# ip_phone_f_power.net
KiCad netlist of a schematic drawn in Altium Designer
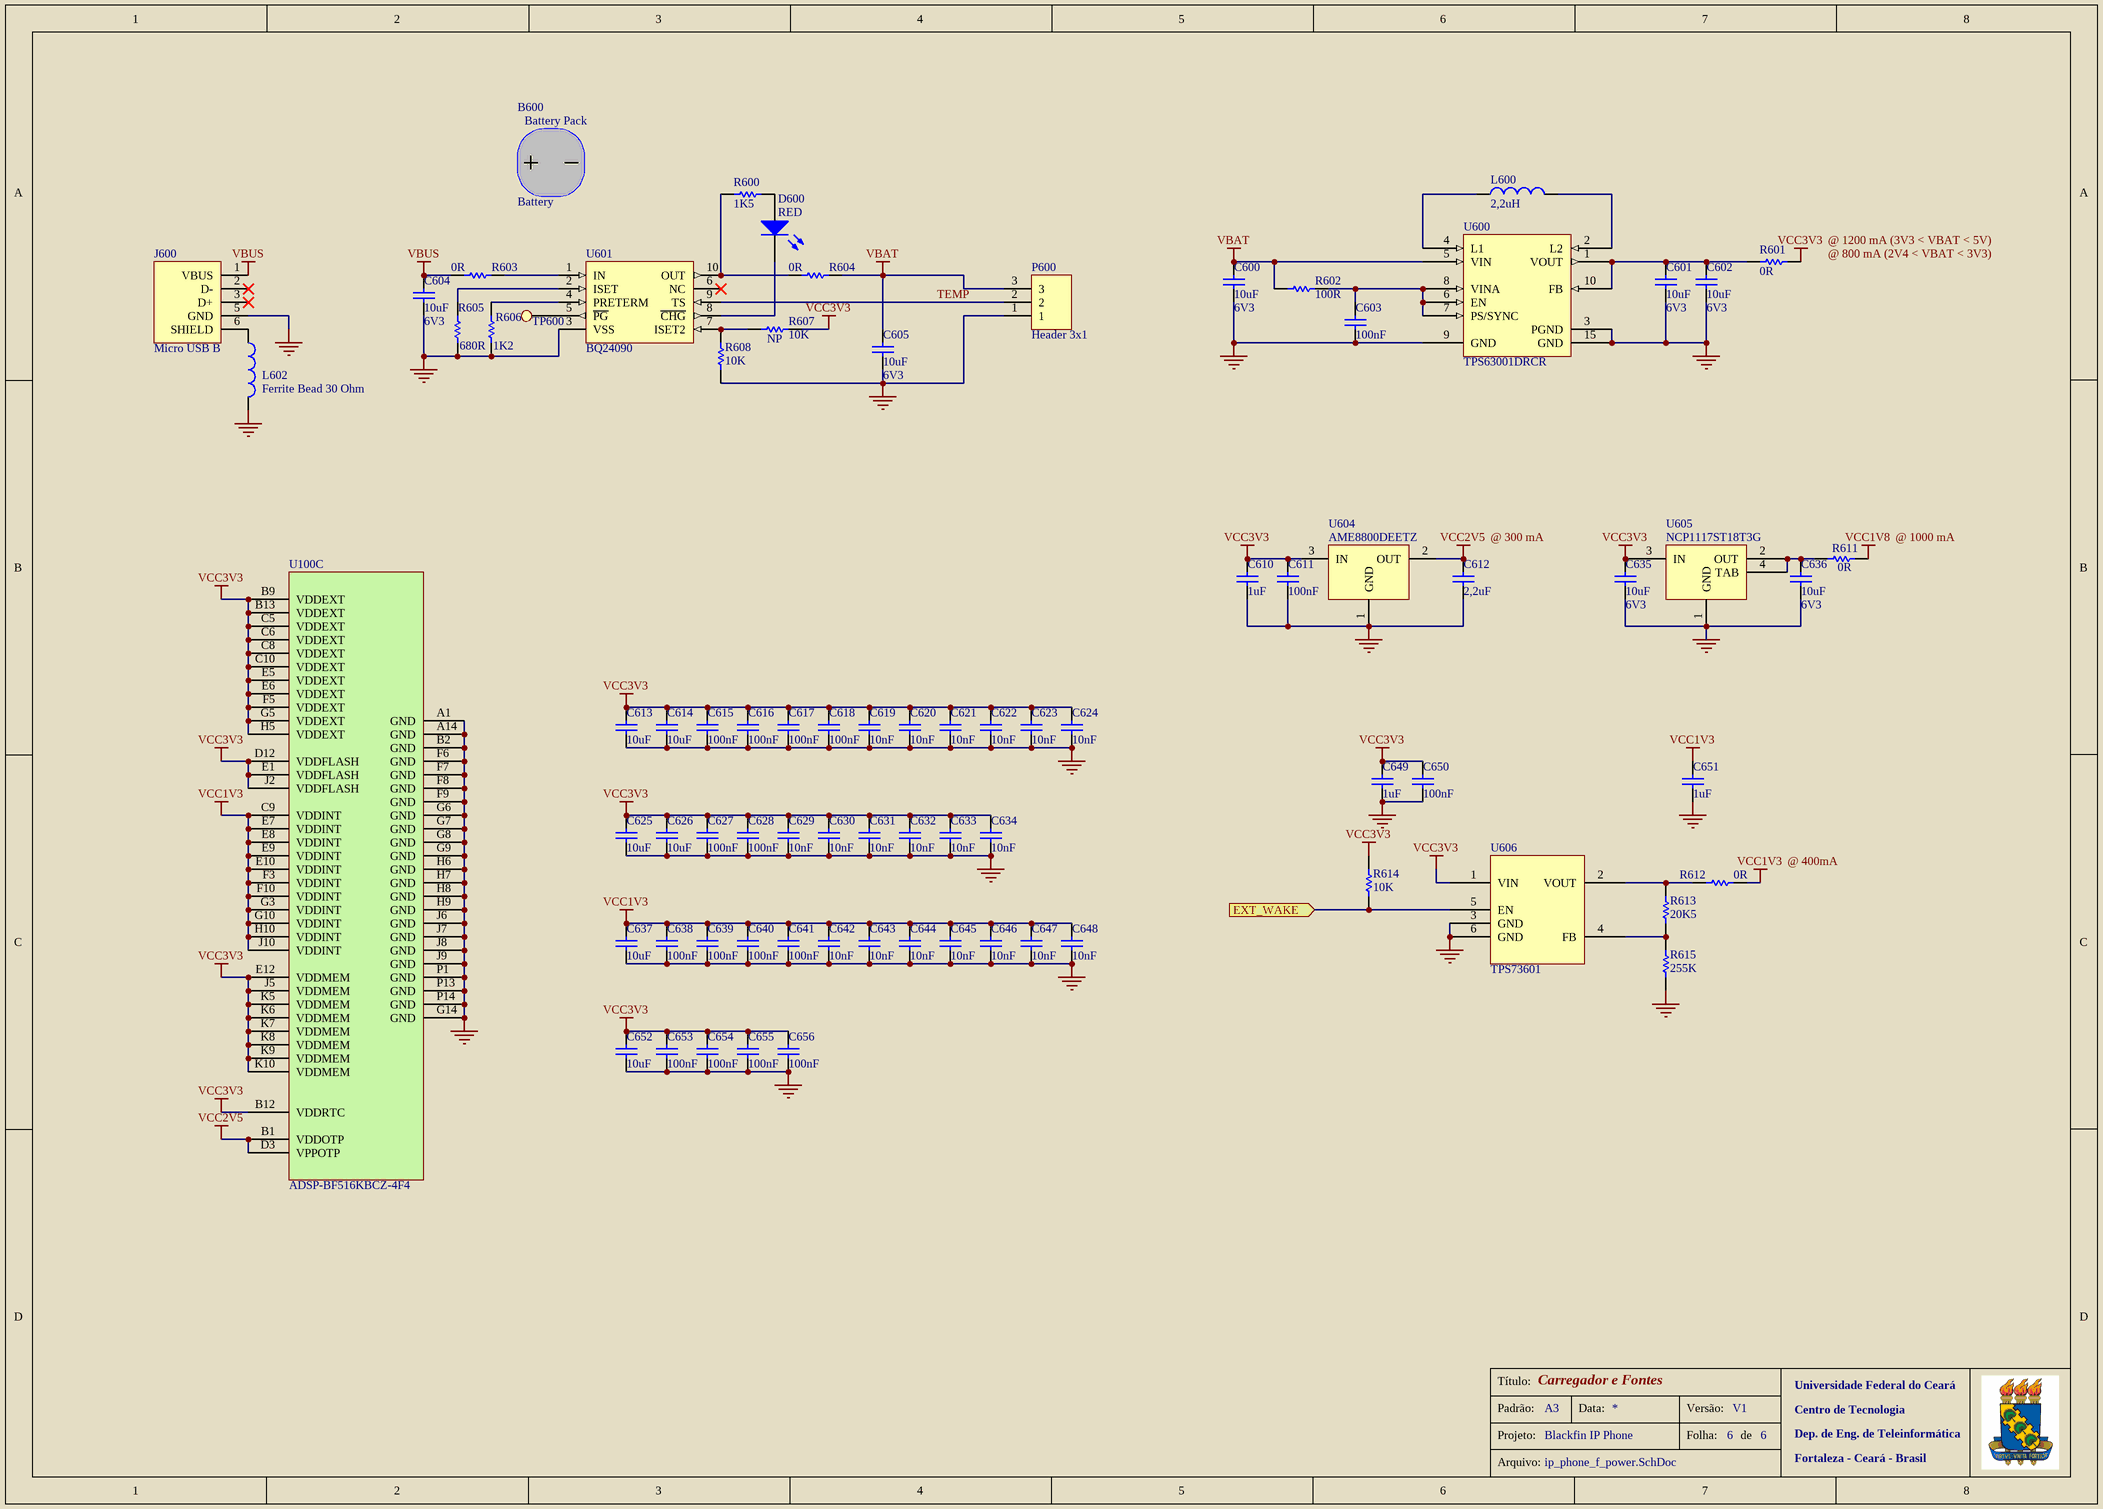
[diagram p0: ip_phone_f_power.SchDoc]

(export (version "E")
  (design (tool "Eeschema 10.0.6"))
  (components
    (comp (ref "B600")
      (value "Battery")
      (description "Li-Polymer battery PL714065, 3.7V 2000mAh cell")
      (fields (field (name "EVENDORPART#") "PC-714065") (field (name "MANUFACTURER") "HOLY TECHNOLOGY"))
      (libsource (lib "ip_phone") (part "Battery"))
    )
    (comp (ref "C600")
      (value "10uF")
      (footprint "ip_phone:CC1608-0603")
      (description "Capacitor SMD/SMT 0603 10uF 6.3volts X5R 20%")
      (fields (field (name "EVENDORPART#") "810-C2012Y5V1A106Z") (field (name "MANUFACTURER") "TDK"))
      (libsource (lib "ip_phone") (part "Capacitor"))
    )
    (comp (ref "C601")
      (value "10uF")
      (footprint "ip_phone:CC1608-0603")
      (description "Capacitor SMD/SMT 0603 10uF 6.3volts X5R 20%")
      (fields (field (name "EVENDORPART#") "810-C2012Y5V1A106Z") (field (name "MANUFACTURER") "TDK"))
      (libsource (lib "ip_phone") (part "Capacitor"))
    )
    (comp (ref "C602")
      (value "10uF")
      (footprint "ip_phone:CC1608-0603")
      (description "Capacitor SMD/SMT 0603 10uF 6.3volts X5R 20%")
      (fields (field (name "EVENDORPART#") "810-C2012Y5V1A106Z") (field (name "MANUFACTURER") "TDK"))
      (libsource (lib "ip_phone") (part "Capacitor"))
    )
    (comp (ref "C603")
      (value "100nF")
      (footprint "ip_phone:CC1005-0402")
      (description "MLCC - SMD/SMT 0.1UF 16V 10% 0402")
      (fields (field (name "EVENDORPART#") "810-C1005X7R1C104K") (field (name "MANUFACTURER") "TDK"))
      (libsource (lib "ip_phone") (part "Capacitor"))
    )
    (comp (ref "C604")
      (value "10uF")
      (footprint "ip_phone:CC1608-0603")
      (description "Capacitor SMD/SMT 0603 10uF 6.3volts X5R 20%")
      (fields (field (name "EVENDORPART#") "810-C2012Y5V1A106Z") (field (name "MANUFACTURER") "TDK"))
      (libsource (lib "ip_phone") (part "Capacitor"))
    )
    (comp (ref "C605")
      (value "10uF")
      (footprint "ip_phone:CC1608-0603")
      (description "Capacitor SMD/SMT 0603 10uF 6.3volts X5R 20%")
      (fields (field (name "EVENDORPART#") "810-C2012Y5V1A106Z") (field (name "MANUFACTURER") "TDK"))
      (libsource (lib "ip_phone") (part "Capacitor"))
    )
    (comp (ref "C610")
      (value "1uF")
      (footprint "ip_phone:CC1005-0402")
      (description "CAP CER 1.0UF 6.3V 20% X5R 0402")
      (fields
        (field (name "EVENDORPART#") "490-1319-1-ND")
        (field (name "MANUFACTURER") "Murata Electronics North America")
      )
      (libsource (lib "ip_phone") (part "Capacitor"))
    )
    (comp (ref "C611")
      (value "100nF")
      (footprint "ip_phone:CC1005-0402")
      (description "MLCC - SMD/SMT 0.1UF 16V 10% 0402")
      (fields (field (name "EVENDORPART#") "810-C1005X7R1C104K") (field (name "MANUFACTURER") "TDK"))
      (libsource (lib "ip_phone") (part "Capacitor"))
    )
    (comp (ref "C612")
      (value "2,2uF")
      (footprint "ip_phone:CC1608-0603")
      (description "Capacitor SMD/SMT 0603 2.2uF 10volts Y5V +80-20%")
      (fields (field (name "EVENDORPART#") "81-GRM188F51A225ZE01") (field (name "MANUFACTURER") "Murata"))
      (libsource (lib "ip_phone") (part "Capacitor"))
    )
    (comp (ref "C613")
      (value "10uF")
      (footprint "ip_phone:CC1608-0603")
      (description "Capacitor SMD/SMT 0603 10uF 6.3volts X5R 20%")
      (fields (field (name "EVENDORPART#") "810-C2012Y5V1A106Z") (field (name "MANUFACTURER") "TDK"))
      (libsource (lib "ip_phone") (part "Capacitor"))
    )
    (comp (ref "C614")
      (value "10uF")
      (footprint "ip_phone:CC1608-0603")
      (description "Capacitor SMD/SMT 0603 10uF 6.3volts X5R 20%")
      (fields (field (name "EVENDORPART#") "810-C2012Y5V1A106Z") (field (name "MANUFACTURER") "TDK"))
      (libsource (lib "ip_phone") (part "Capacitor"))
    )
    (comp (ref "C615")
      (value "100nF")
      (footprint "ip_phone:CC1005-0402")
      (description "MLCC - SMD/SMT 0.1UF 16V 10% 0402")
      (fields (field (name "EVENDORPART#") "810-C1005X7R1C104K") (field (name "MANUFACTURER") "TDK"))
      (libsource (lib "ip_phone") (part "Capacitor"))
    )
    (comp (ref "C616")
      (value "100nF")
      (footprint "ip_phone:CC1005-0402")
      (description "MLCC - SMD/SMT 0.1UF 16V 10% 0402")
      (fields (field (name "EVENDORPART#") "810-C1005X7R1C104K") (field (name "MANUFACTURER") "TDK"))
      (libsource (lib "ip_phone") (part "Capacitor"))
    )
    (comp (ref "C617")
      (value "100nF")
      (footprint "ip_phone:CC1005-0402")
      (description "MLCC - SMD/SMT 0.1UF 16V 10% 0402")
      (fields (field (name "EVENDORPART#") "810-C1005X7R1C104K") (field (name "MANUFACTURER") "TDK"))
      (libsource (lib "ip_phone") (part "Capacitor"))
    )
    (comp (ref "C618")
      (value "100nF")
      (footprint "ip_phone:CC1005-0402")
      (description "MLCC - SMD/SMT 0.1UF 16V 10% 0402")
      (fields (field (name "EVENDORPART#") "810-C1005X7R1C104K") (field (name "MANUFACTURER") "TDK"))
      (libsource (lib "ip_phone") (part "Capacitor"))
    )
    (comp (ref "C619")
      (value "10nF")
      (footprint "ip_phone:CC1005-0402")
      (description "Capacitor SMD/SMT 0402 0.01uF 16volts X7R 10%")
      (fields (field (name "EVENDORPART#") "810-C1005X7R1C103K") (field (name "MANUFACTURER") "TDK"))
      (libsource (lib "ip_phone") (part "Capacitor"))
    )
    (comp (ref "C620")
      (value "10nF")
      (footprint "ip_phone:CC1005-0402")
      (description "Capacitor SMD/SMT 0402 0.01uF 16volts X7R 10%")
      (fields (field (name "EVENDORPART#") "810-C1005X7R1C103K") (field (name "MANUFACTURER") "TDK"))
      (libsource (lib "ip_phone") (part "Capacitor"))
    )
    (comp (ref "C621")
      (value "10nF")
      (footprint "ip_phone:CC1005-0402")
      (description "Capacitor SMD/SMT 0402 0.01uF 16volts X7R 10%")
      (fields (field (name "EVENDORPART#") "810-C1005X7R1C103K") (field (name "MANUFACTURER") "TDK"))
      (libsource (lib "ip_phone") (part "Capacitor"))
    )
    (comp (ref "C622")
      (value "10nF")
      (footprint "ip_phone:CC1005-0402")
      (description "Capacitor SMD/SMT 0402 0.01uF 16volts X7R 10%")
      (fields (field (name "EVENDORPART#") "810-C1005X7R1C103K") (field (name "MANUFACTURER") "TDK"))
      (libsource (lib "ip_phone") (part "Capacitor"))
    )
    (comp (ref "C623")
      (value "10nF")
      (footprint "ip_phone:CC1005-0402")
      (description "Capacitor SMD/SMT 0402 0.01uF 16volts X7R 10%")
      (fields (field (name "EVENDORPART#") "810-C1005X7R1C103K") (field (name "MANUFACTURER") "TDK"))
      (libsource (lib "ip_phone") (part "Capacitor"))
    )
    (comp (ref "C624")
      (value "10nF")
      (footprint "ip_phone:CC1005-0402")
      (description "Capacitor SMD/SMT 0402 0.01uF 16volts X7R 10%")
      (fields (field (name "EVENDORPART#") "810-C1005X7R1C103K") (field (name "MANUFACTURER") "TDK"))
      (libsource (lib "ip_phone") (part "Capacitor"))
    )
    (comp (ref "C625")
      (value "10uF")
      (footprint "ip_phone:CC1608-0603")
      (description "Capacitor SMD/SMT 0603 10uF 6.3volts X5R 20%")
      (fields (field (name "EVENDORPART#") "810-C2012Y5V1A106Z") (field (name "MANUFACTURER") "TDK"))
      (libsource (lib "ip_phone") (part "Capacitor"))
    )
    (comp (ref "C626")
      (value "10uF")
      (footprint "ip_phone:CC1608-0603")
      (description "Capacitor SMD/SMT 0603 10uF 6.3volts X5R 20%")
      (fields (field (name "EVENDORPART#") "810-C2012Y5V1A106Z") (field (name "MANUFACTURER") "TDK"))
      (libsource (lib "ip_phone") (part "Capacitor"))
    )
    (comp (ref "C627")
      (value "100nF")
      (footprint "ip_phone:CC1005-0402")
      (description "MLCC - SMD/SMT 0.1UF 16V 10% 0402")
      (fields (field (name "EVENDORPART#") "810-C1005X7R1C104K") (field (name "MANUFACTURER") "TDK"))
      (libsource (lib "ip_phone") (part "Capacitor"))
    )
    (comp (ref "C628")
      (value "100nF")
      (footprint "ip_phone:CC1005-0402")
      (description "MLCC - SMD/SMT 0.1UF 16V 10% 0402")
      (fields (field (name "EVENDORPART#") "810-C1005X7R1C104K") (field (name "MANUFACTURER") "TDK"))
      (libsource (lib "ip_phone") (part "Capacitor"))
    )
    (comp (ref "C629")
      (value "10nF")
      (footprint "ip_phone:CC1005-0402")
      (description "Capacitor SMD/SMT 0402 0.01uF 16volts X7R 10%")
      (fields (field (name "EVENDORPART#") "810-C1005X7R1C103K") (field (name "MANUFACTURER") "TDK"))
      (libsource (lib "ip_phone") (part "Capacitor"))
    )
    (comp (ref "C630")
      (value "10nF")
      (footprint "ip_phone:CC1005-0402")
      (description "Capacitor SMD/SMT 0402 0.01uF 16volts X7R 10%")
      (fields (field (name "EVENDORPART#") "810-C1005X7R1C103K") (field (name "MANUFACTURER") "TDK"))
      (libsource (lib "ip_phone") (part "Capacitor"))
    )
    (comp (ref "C631")
      (value "10nF")
      (footprint "ip_phone:CC1005-0402")
      (description "Capacitor SMD/SMT 0402 0.01uF 16volts X7R 10%")
      (fields (field (name "EVENDORPART#") "810-C1005X7R1C103K") (field (name "MANUFACTURER") "TDK"))
      (libsource (lib "ip_phone") (part "Capacitor"))
    )
    (comp (ref "C632")
      (value "10nF")
      (footprint "ip_phone:CC1005-0402")
      (description "Capacitor SMD/SMT 0402 0.01uF 16volts X7R 10%")
      (fields (field (name "EVENDORPART#") "810-C1005X7R1C103K") (field (name "MANUFACTURER") "TDK"))
      (libsource (lib "ip_phone") (part "Capacitor"))
    )
    (comp (ref "C633")
      (value "10nF")
      (footprint "ip_phone:CC1005-0402")
      (description "Capacitor SMD/SMT 0402 0.01uF 16volts X7R 10%")
      (fields (field (name "EVENDORPART#") "810-C1005X7R1C103K") (field (name "MANUFACTURER") "TDK"))
      (libsource (lib "ip_phone") (part "Capacitor"))
    )
    (comp (ref "C634")
      (value "10nF")
      (footprint "ip_phone:CC1005-0402")
      (description "Capacitor SMD/SMT 0402 0.01uF 16volts X7R 10%")
      (fields (field (name "EVENDORPART#") "810-C1005X7R1C103K") (field (name "MANUFACTURER") "TDK"))
      (libsource (lib "ip_phone") (part "Capacitor"))
    )
    (comp (ref "C635")
      (value "10uF")
      (footprint "ip_phone:CC1608-0603")
      (description "Capacitor SMD/SMT 0603 10uF 6.3volts X5R 20%")
      (fields (field (name "EVENDORPART#") "810-C2012Y5V1A106Z") (field (name "MANUFACTURER") "TDK"))
      (libsource (lib "ip_phone") (part "Capacitor"))
    )
    (comp (ref "C636")
      (value "10uF")
      (footprint "ip_phone:CC1608-0603")
      (description "Capacitor SMD/SMT 0603 10uF 6.3volts X5R 20%")
      (fields (field (name "EVENDORPART#") "810-C2012Y5V1A106Z") (field (name "MANUFACTURER") "TDK"))
      (libsource (lib "ip_phone") (part "Capacitor"))
    )
    (comp (ref "C637")
      (value "10uF")
      (footprint "ip_phone:CC1608-0603")
      (description "Capacitor SMD/SMT 0603 10uF 6.3volts X5R 20%")
      (fields (field (name "EVENDORPART#") "810-C2012Y5V1A106Z") (field (name "MANUFACTURER") "TDK"))
      (libsource (lib "ip_phone") (part "Capacitor"))
    )
    (comp (ref "C638")
      (value "100nF")
      (footprint "ip_phone:CC1005-0402")
      (description "MLCC - SMD/SMT 0.1UF 16V 10% 0402")
      (fields (field (name "EVENDORPART#") "810-C1005X7R1C104K") (field (name "MANUFACTURER") "TDK"))
      (libsource (lib "ip_phone") (part "Capacitor"))
    )
    (comp (ref "C639")
      (value "100nF")
      (footprint "ip_phone:CC1005-0402")
      (description "MLCC - SMD/SMT 0.1UF 16V 10% 0402")
      (fields (field (name "EVENDORPART#") "810-C1005X7R1C104K") (field (name "MANUFACTURER") "TDK"))
      (libsource (lib "ip_phone") (part "Capacitor"))
    )
    (comp (ref "C640")
      (value "100nF")
      (footprint "ip_phone:CC1005-0402")
      (description "MLCC - SMD/SMT 0.1UF 16V 10% 0402")
      (fields (field (name "EVENDORPART#") "810-C1005X7R1C104K") (field (name "MANUFACTURER") "TDK"))
      (libsource (lib "ip_phone") (part "Capacitor"))
    )
    (comp (ref "C641")
      (value "100nF")
      (footprint "ip_phone:CC1005-0402")
      (description "MLCC - SMD/SMT 0.1UF 16V 10% 0402")
      (fields (field (name "EVENDORPART#") "810-C1005X7R1C104K") (field (name "MANUFACTURER") "TDK"))
      (libsource (lib "ip_phone") (part "Capacitor"))
    )
    (comp (ref "C642")
      (value "10nF")
      (footprint "ip_phone:CC1005-0402")
      (description "Capacitor SMD/SMT 0402 0.01uF 16volts X7R 10%")
      (fields (field (name "EVENDORPART#") "810-C1005X7R1C103K") (field (name "MANUFACTURER") "TDK"))
      (libsource (lib "ip_phone") (part "Capacitor"))
    )
    (comp (ref "C643")
      (value "10nF")
      (footprint "ip_phone:CC1005-0402")
      (description "Capacitor SMD/SMT 0402 0.01uF 16volts X7R 10%")
      (fields (field (name "EVENDORPART#") "810-C1005X7R1C103K") (field (name "MANUFACTURER") "TDK"))
      (libsource (lib "ip_phone") (part "Capacitor"))
    )
    (comp (ref "C644")
      (value "10nF")
      (footprint "ip_phone:CC1005-0402")
      (description "Capacitor SMD/SMT 0402 0.01uF 16volts X7R 10%")
      (fields (field (name "EVENDORPART#") "810-C1005X7R1C103K") (field (name "MANUFACTURER") "TDK"))
      (libsource (lib "ip_phone") (part "Capacitor"))
    )
    (comp (ref "C645")
      (value "10nF")
      (footprint "ip_phone:CC1005-0402")
      (description "Capacitor SMD/SMT 0402 0.01uF 16volts X7R 10%")
      (fields (field (name "EVENDORPART#") "810-C1005X7R1C103K") (field (name "MANUFACTURER") "TDK"))
      (libsource (lib "ip_phone") (part "Capacitor"))
    )
    (comp (ref "C646")
      (value "10nF")
      (footprint "ip_phone:CC1005-0402")
      (description "Capacitor SMD/SMT 0402 0.01uF 16volts X7R 10%")
      (fields (field (name "EVENDORPART#") "810-C1005X7R1C103K") (field (name "MANUFACTURER") "TDK"))
      (libsource (lib "ip_phone") (part "Capacitor"))
    )
    (comp (ref "C647")
      (value "10nF")
      (footprint "ip_phone:CC1005-0402")
      (description "Capacitor SMD/SMT 0402 0.01uF 16volts X7R 10%")
      (fields (field (name "EVENDORPART#") "810-C1005X7R1C103K") (field (name "MANUFACTURER") "TDK"))
      (libsource (lib "ip_phone") (part "Capacitor"))
    )
    (comp (ref "C648")
      (value "10nF")
      (footprint "ip_phone:CC1005-0402")
      (description "Capacitor SMD/SMT 0402 0.01uF 16volts X7R 10%")
      (fields (field (name "EVENDORPART#") "810-C1005X7R1C103K") (field (name "MANUFACTURER") "TDK"))
      (libsource (lib "ip_phone") (part "Capacitor"))
    )
    (comp (ref "C649")
      (value "1uF")
      (footprint "ip_phone:CC1005-0402")
      (description "CAP CER 1.0UF 6.3V 20% X5R 0402")
      (fields
        (field (name "EVENDORPART#") "490-1319-1-ND")
        (field (name "MANUFACTURER") "Murata Electronics North America")
      )
      (libsource (lib "ip_phone") (part "Capacitor"))
    )
    (comp (ref "C650")
      (value "100nF")
      (footprint "ip_phone:CC1005-0402")
      (description "MLCC - SMD/SMT 0.1UF 16V 10% 0402")
      (fields (field (name "EVENDORPART#") "810-C1005X7R1C104K") (field (name "MANUFACTURER") "TDK"))
      (libsource (lib "ip_phone") (part "Capacitor"))
    )
    (comp (ref "C651")
      (value "1uF")
      (footprint "ip_phone:CC1005-0402")
      (description "CAP CER 1.0UF 6.3V 20% X5R 0402")
      (fields
        (field (name "EVENDORPART#") "490-1319-1-ND")
        (field (name "MANUFACTURER") "Murata Electronics North America")
      )
      (libsource (lib "ip_phone") (part "Capacitor"))
    )
    (comp (ref "C652")
      (value "10uF")
      (footprint "ip_phone:CC1608-0603")
      (description "Capacitor SMD/SMT 0603 10uF 6.3volts X5R 20%")
      (fields (field (name "EVENDORPART#") "810-C2012Y5V1A106Z") (field (name "MANUFACTURER") "TDK"))
      (libsource (lib "ip_phone") (part "Capacitor"))
    )
    (comp (ref "C653")
      (value "100nF")
      (footprint "ip_phone:CC1005-0402")
      (description "MLCC - SMD/SMT 0.1UF 16V 10% 0402")
      (fields (field (name "EVENDORPART#") "810-C1005X7R1C104K") (field (name "MANUFACTURER") "TDK"))
      (libsource (lib "ip_phone") (part "Capacitor"))
    )
    (comp (ref "C654")
      (value "100nF")
      (footprint "ip_phone:CC1005-0402")
      (description "MLCC - SMD/SMT 0.1UF 16V 10% 0402")
      (fields (field (name "EVENDORPART#") "810-C1005X7R1C104K") (field (name "MANUFACTURER") "TDK"))
      (libsource (lib "ip_phone") (part "Capacitor"))
    )
    (comp (ref "C655")
      (value "100nF")
      (footprint "ip_phone:CC1005-0402")
      (description "MLCC - SMD/SMT 0.1UF 16V 10% 0402")
      (fields (field (name "EVENDORPART#") "810-C1005X7R1C104K") (field (name "MANUFACTURER") "TDK"))
      (libsource (lib "ip_phone") (part "Capacitor"))
    )
    (comp (ref "C656")
      (value "100nF")
      (footprint "ip_phone:CC1005-0402")
      (description "MLCC - SMD/SMT 0.1UF 16V 10% 0402")
      (fields (field (name "EVENDORPART#") "810-C1005X7R1C104K") (field (name "MANUFACTURER") "TDK"))
      (libsource (lib "ip_phone") (part "Capacitor"))
    )
    (comp (ref "D600")
      (value "RED")
      (footprint "ip_phone:LED 3MM VERMELHO PF-D3")
      (description "LED")
      (fields (field (name "PART#") "TLHR4205") (field (name "MANUFACTURER") "Vishay Semiconductors"))
      (libsource (lib "ip_phone") (part "LED"))
    )
    (comp (ref "J600")
      (value "Micro USB B")
      (footprint "ip_phone:Micro USB")
      (description "USB Connectors 5P Quick Connect Micro USB TypeB Rcpt")
      (fields (field (name "MANUFACTURER") "FCI") (field (name "PART#") "10103594-0001LF"))
      (libsource (lib "ip_phone") (part "CON_Micro_USB"))
    )
    (comp (ref "L600")
      (value "2,2uH")
      (footprint "ip_phone:POWER INDUCTOR")
      (description "IND POWER 2.2UH 1.5A SMD")
      (fields (field (name "EVENDORPART#") "445-3233-1-ND") (field (name "MANUFACTURER") "TDK"))
      (libsource (lib "ip_phone") (part "Inductor"))
    )
    (comp (ref "L602")
      (value "Ferrite Bead 30 Ohm")
      (footprint "ip_phone:INDUTOR_0603")
      (description "EMI/RFI Suppressors & Ferrites 0603 30 OHM")
      (fields (field (name "EVENDORPART#") "81-BLM11P300S") (field (name "MANUFACTURER") "Murata"))
      (libsource (lib "ip_phone") (part "Inductor"))
    )
    (comp (ref "P600")
      (value "Header 3x1")
      (footprint "ip_phone:HEADER 3x1")
      (description "CONN HEADER 3POS 2.5MM R/A SMD")
      (fields
        (field (name "MANUFACTURER") "JST Sales America Inc")
        (field (name "PART#") "S3B-XH-SM4-TB(LF)(SN)")
      )
      (libsource (lib "ip_phone") (part "CON_HEADER_3x1"))
    )
    (comp (ref "R600")
      (value "1K5")
      (footprint "ip_phone:CR1608-0603")
      (description "Thick Film Resistors 1.5KOHM 5% 1/10W")
      (fields (field (name "EVENDORPART#") "52-CR0603-JW-152GLF") (field (name "MANUFACTURER") "Bourns"))
      (libsource (lib "ip_phone") (part "Resistor"))
    )
    (comp (ref "R601")
      (value "0R")
      (footprint "ip_phone:CR3225-1210")
      (description "Thick Film Resistors ZERO OHM JUMPER 1210")
      (fields (field (name "EVENDORPART#") "660-RK73Z2ETTD") (field (name "MANUFACTURER") "KOA Speer"))
      (libsource (lib "ip_phone") (part "Resistor"))
    )
    (comp (ref "R602")
      (value "100R")
      (footprint "ip_phone:CR1608-0603")
      (description "Thick Film Resistors 1/16WATT 100R 0402")
      (fields (field (name "EVENDORPART#") "652-CR0603-JW-101GLF") (field (name "MANUFACTURER") "Bourns"))
      (libsource (lib "ip_phone") (part "Resistor"))
    )
    (comp (ref "R603")
      (value "0R")
      (footprint "ip_phone:CR1608-0603")
      (description "Thick Film Resistors ZERO OHM")
      (fields (field (name "EVENDORPART#") "652-CR0603-J/-000ELF") (field (name "MANUFACTURER") "Bourns"))
      (libsource (lib "ip_phone") (part "Resistor"))
    )
    (comp (ref "R604")
      (value "0R")
      (footprint "ip_phone:CR1608-0603")
      (description "Thick Film Resistors ZERO OHM")
      (fields (field (name "EVENDORPART#") "652-CR0603-J/-000ELF") (field (name "MANUFACTURER") "Bourns"))
      (libsource (lib "ip_phone") (part "Resistor"))
    )
    (comp (ref "R605")
      (value "680R")
      (footprint "ip_phone:CR1005-0402")
      (description "Thick Film Resistors SMD 0402 680 5%  1/16 W")
      (fields (field (name "EVENDORPART#") "311-680JRCT-ND") (field (name "MANUFACTURER") "Yageo"))
      (libsource (lib "ip_phone") (part "Resistor"))
    )
    (comp (ref "R606")
      (value "1K2")
      (footprint "ip_phone:CR1005-0402")
      (description "Thick Film Resistors SMD 0402 1K2 5%  1/16 W")
      (fields (field (name "EVENDORPART#") "311-1.2KJRCT-ND") (field (name "MANUFACTURER") "Yageo"))
      (libsource (lib "ip_phone") (part "Resistor"))
    )
    (comp (ref "R607")
      (value "10K")
      (footprint "ip_phone:CR1005-0402")
      (description "Thick Film Resistors SMD 0402 10k 5%  1/16 W")
      (fields
        (field (name "EVENDORPART#") "311-10KJRCT-ND")
        (field (name "MANUFACTURER") "Yageo")
        (field (name "NP") "NP")
      )
      (libsource (lib "ip_phone") (part "Resistor"))
    )
    (comp (ref "R608")
      (value "10K")
      (footprint "ip_phone:CR1005-0402")
      (description "Thick Film Resistors SMD 0402 10k 5%  1/16 W")
      (fields (field (name "EVENDORPART#") "311-10KJRCT-ND") (field (name "MANUFACTURER") "Yageo"))
      (libsource (lib "ip_phone") (part "Resistor"))
    )
    (comp (ref "R611")
      (value "0R")
      (footprint "ip_phone:CR3225-1210")
      (description "Thick Film Resistors ZERO OHM JUMPER 1210")
      (fields (field (name "EVENDORPART#") "660-RK73Z2ETTD") (field (name "MANUFACTURER") "KOA Speer"))
      (libsource (lib "ip_phone") (part "Resistor"))
    )
    (comp (ref "R612")
      (value "0R")
      (footprint "ip_phone:CR1608-0603")
      (description "Thick Film Resistors ZERO OHM")
      (fields (field (name "EVENDORPART#") "652-CR0603-J/-000ELF") (field (name "MANUFACTURER") "Bourns"))
      (libsource (lib "ip_phone") (part "Resistor"))
    )
    (comp (ref "R613")
      (value "20K5")
      (footprint "ip_phone:CR1005-0402")
      (description "RES 20.5K OHM 1/10W 1% 0402 SMD")
      (fields (field (name "EVENDORPART#") "P20.5KLCT-ND") (field (name "MANUFACTURER") "Panasonic - ECG"))
      (libsource (lib "ip_phone") (part "Resistor"))
    )
    (comp (ref "R614")
      (value "10K")
      (footprint "ip_phone:CR1005-0402")
      (description "Thick Film Resistors SMD 0402 10k 5%  1/16 W")
      (fields (field (name "EVENDORPART#") "311-10KJRCT-ND") (field (name "MANUFACTURER") "Yageo"))
      (libsource (lib "ip_phone") (part "Resistor"))
    )
    (comp (ref "R615")
      (value "255K")
      (footprint "ip_phone:CR1005-0402")
      (description "RES 255K OHM 1/10W 1% 0402 SMD")
      (fields (field (name "EVENDORPART#") "P255KLCT-ND") (field (name "MANUFACTURER") "Panasonic - ECG"))
      (libsource (lib "ip_phone") (part "Resistor"))
    )
    (comp (ref "TP600")
      (value "Test Point")
      (footprint "ip_phone:Test Point")
      (fields (field (name "EVENDORPART#") "NÃO SE APLICA"))
      (libsource (lib "ip_phone") (part "Test Point"))
    )
    (comp (ref "U100")
      (value "ADSP-BF516KBCZ-4F4")
      (footprint "ip_phone:BGA168")
      (description "Low Power Blackfin with Advanced Embedded Connectivity")
      (fields (field (name "MANUFACTURER") "Analog Device"))
      (libsource (lib "ip_phone") (part "ADSP-BF516KBCZ-4F4"))
    )
    (comp (ref "U600")
      (value "TPS63001DRCR")
      (footprint "ip_phone:SON10")
      (description "HIGH EFFICIENT SINGLE INDUCTOR BUCK-BOOST CONVERTER WITH 1.8-A SWITCHES")
      (fields
        (field (name "EVENDORPART#") "296-19643-1-ND")
        (field (name "MANUFACTURER") "Texas Instruments")
      )
      (libsource (lib "ip_phone") (part "TPS63001DRCR"))
    )
    (comp (ref "U601")
      (value "BQ24090")
      (footprint "ip_phone:MSOP10")
      (description "1A,Sgl Inp,Sgl Cell Li-Ion Batt Charger")
      (fields (field (name "MANUFACTURER") "Texas Instruments") (field (name "PART#") "BQ24090DGQT"))
      (libsource (lib "ip_phone") (part "BQ24090"))
    )
    (comp (ref "U604")
      (value "AME8800DEETZ")
      (footprint "ip_phone:SOT-23")
      (description "Low Dropout (LDO) Regulators 2.5V 300mA CMOS")
      (fields (field (name "EVENDORPART#") "827-AME8800DEETZ") (field (name "MANUFACTURER") "AME"))
      (libsource (lib "ip_phone") (part "AME8800DEETZ"))
    )
    (comp (ref "U605")
      (value "NCP1117ST18T3G")
      (footprint "ip_phone:SOT223")
      (description "Low Dropout (LDO) Regulators 1.8V 1A Positive")
      (fields
        (field (name "EVENDORPART#") "863-NCP1117ST18T3G")
        (field (name "MANUFACTURER") "ON Semiconductor")
      )
      (libsource (lib "ip_phone") (part "NCP1117ST18T3G"))
    )
    (comp (ref "U606")
      (value "TPS73601")
      (footprint "ip_phone:SOT223 - 6P")
      (description "LDO Regulator")
      (fields (field (name "PART#") "TPS73601DCQR") (field (name "EVENDORPART#") "595-TPS73601DCQR"))
      (libsource (lib "ip_phone") (part "TPS73601"))
    )
  )
  (nets
    (net (code "1") (name "/EXT_WAKE") (class "Default")
      (node (ref "R614") (pin "2") (pinfunction "2_2") (pintype "passive"))
      (node (ref "U606") (pin "5") (pinfunction "EN_5") (pintype "passive"))
    )
    (net (code "2") (name "/TEMP") (class "Default")
      (node (ref "P600") (pin "2") (pinfunction "2_2") (pintype "passive"))
      (node (ref "U601") (pin "9") (pinfunction "TS_9") (pintype "input"))
    )
    (net (code "3") (name "GND") (class "Default")
      (node (ref "C600") (pin "1") (pinfunction "1_1") (pintype "passive"))
      (node (ref "C601") (pin "1") (pinfunction "1_1") (pintype "passive"))
      (node (ref "C602") (pin "1") (pinfunction "1_1") (pintype "passive"))
      (node (ref "C603") (pin "1") (pinfunction "1_1") (pintype "passive"))
      (node (ref "C604") (pin "1") (pinfunction "1_1") (pintype "passive"))
      (node (ref "C605") (pin "1") (pinfunction "1_1") (pintype "passive"))
      (node (ref "C610") (pin "2") (pinfunction "2_2") (pintype "passive"))
      (node (ref "C611") (pin "1") (pinfunction "1_1") (pintype "passive"))
      (node (ref "C612") (pin "1") (pinfunction "1_1") (pintype "passive"))
      (node (ref "C613") (pin "1") (pinfunction "1_1") (pintype "passive"))
      (node (ref "C614") (pin "1") (pinfunction "1_1") (pintype "passive"))
      (node (ref "C615") (pin "1") (pinfunction "1_1") (pintype "passive"))
      (node (ref "C616") (pin "1") (pinfunction "1_1") (pintype "passive"))
      (node (ref "C617") (pin "1") (pinfunction "1_1") (pintype "passive"))
      (node (ref "C618") (pin "1") (pinfunction "1_1") (pintype "passive"))
      (node (ref "C619") (pin "1") (pinfunction "1_1") (pintype "passive"))
      (node (ref "C620") (pin "1") (pinfunction "1_1") (pintype "passive"))
      (node (ref "C621") (pin "1") (pinfunction "1_1") (pintype "passive"))
      (node (ref "C622") (pin "1") (pinfunction "1_1") (pintype "passive"))
      (node (ref "C623") (pin "1") (pinfunction "1_1") (pintype "passive"))
      (node (ref "C624") (pin "1") (pinfunction "1_1") (pintype "passive"))
      (node (ref "C625") (pin "1") (pinfunction "1_1") (pintype "passive"))
      (node (ref "C626") (pin "1") (pinfunction "1_1") (pintype "passive"))
      (node (ref "C627") (pin "1") (pinfunction "1_1") (pintype "passive"))
      (node (ref "C628") (pin "1") (pinfunction "1_1") (pintype "passive"))
      (node (ref "C629") (pin "1") (pinfunction "1_1") (pintype "passive"))
      (node (ref "C630") (pin "1") (pinfunction "1_1") (pintype "passive"))
      (node (ref "C631") (pin "1") (pinfunction "1_1") (pintype "passive"))
      (node (ref "C632") (pin "1") (pinfunction "1_1") (pintype "passive"))
      (node (ref "C633") (pin "1") (pinfunction "1_1") (pintype "passive"))
      (node (ref "C634") (pin "1") (pinfunction "1_1") (pintype "passive"))
      (node (ref "C635") (pin "1") (pinfunction "1_1") (pintype "passive"))
      (node (ref "C636") (pin "1") (pinfunction "1_1") (pintype "passive"))
      (node (ref "C637") (pin "1") (pinfunction "1_1") (pintype "passive"))
      (node (ref "C638") (pin "1") (pinfunction "1_1") (pintype "passive"))
      (node (ref "C639") (pin "1") (pinfunction "1_1") (pintype "passive"))
      (node (ref "C640") (pin "1") (pinfunction "1_1") (pintype "passive"))
      (node (ref "C641") (pin "1") (pinfunction "1_1") (pintype "passive"))
      (node (ref "C642") (pin "1") (pinfunction "1_1") (pintype "passive"))
      (node (ref "C643") (pin "1") (pinfunction "1_1") (pintype "passive"))
      (node (ref "C644") (pin "1") (pinfunction "1_1") (pintype "passive"))
      (node (ref "C645") (pin "1") (pinfunction "1_1") (pintype "passive"))
      (node (ref "C646") (pin "1") (pinfunction "1_1") (pintype "passive"))
      (node (ref "C647") (pin "1") (pinfunction "1_1") (pintype "passive"))
      (node (ref "C648") (pin "1") (pinfunction "1_1") (pintype "passive"))
      (node (ref "C649") (pin "2") (pinfunction "2_2") (pintype "passive"))
      (node (ref "C650") (pin "1") (pinfunction "1_1") (pintype "passive"))
      (node (ref "C651") (pin "2") (pinfunction "2_2") (pintype "passive"))
      (node (ref "C652") (pin "1") (pinfunction "1_1") (pintype "passive"))
      (node (ref "C653") (pin "1") (pinfunction "1_1") (pintype "passive"))
      (node (ref "C654") (pin "1") (pinfunction "1_1") (pintype "passive"))
      (node (ref "C655") (pin "1") (pinfunction "1_1") (pintype "passive"))
      (node (ref "C656") (pin "1") (pinfunction "1_1") (pintype "passive"))
      (node (ref "J600") (pin "5") (pinfunction "GND_5") (pintype "passive"))
      (node (ref "L602") (pin "2") (pinfunction "2_2") (pintype "passive"))
      (node (ref "P600") (pin "1") (pinfunction "1_1") (pintype "passive"))
      (node (ref "R605") (pin "1") (pinfunction "1_1") (pintype "passive"))
      (node (ref "R606") (pin "2") (pinfunction "2_2") (pintype "passive"))
      (node (ref "R608") (pin "2") (pinfunction "2_2") (pintype "passive"))
      (node (ref "R615") (pin "1") (pinfunction "1_1") (pintype "passive"))
      (node (ref "U100") (pin "A1") (pinfunction "GND_A1") (pintype "power_in"))
      (node (ref "U100") (pin "A14") (pinfunction "GND_A14") (pintype "power_in"))
      (node (ref "U100") (pin "B2") (pinfunction "GND_B2") (pintype "power_in"))
      (node (ref "U100") (pin "F6") (pinfunction "GND_F6") (pintype "power_in"))
      (node (ref "U100") (pin "F7") (pinfunction "GND_F7") (pintype "power_in"))
      (node (ref "U100") (pin "F8") (pinfunction "GND_F8") (pintype "power_in"))
      (node (ref "U100") (pin "F9") (pinfunction "GND_F9") (pintype "power_in"))
      (node (ref "U100") (pin "G14") (pinfunction "GND_G14") (pintype "power_in"))
      (node (ref "U100") (pin "G6") (pinfunction "GND_G6") (pintype "power_in"))
      (node (ref "U100") (pin "G7") (pinfunction "GND_G7") (pintype "power_in"))
      (node (ref "U100") (pin "G8") (pinfunction "GND_G8") (pintype "power_in"))
      (node (ref "U100") (pin "G9") (pinfunction "GND_G9") (pintype "power_in"))
      (node (ref "U100") (pin "H6") (pinfunction "GND_H6") (pintype "power_in"))
      (node (ref "U100") (pin "H7") (pinfunction "GND_H7") (pintype "power_in"))
      (node (ref "U100") (pin "H8") (pinfunction "GND_H8") (pintype "power_in"))
      (node (ref "U100") (pin "H9") (pinfunction "GND_H9") (pintype "power_in"))
      (node (ref "U100") (pin "J6") (pinfunction "GND_J6") (pintype "power_in"))
      (node (ref "U100") (pin "J7") (pinfunction "GND_J7") (pintype "power_in"))
      (node (ref "U100") (pin "J8") (pinfunction "GND_J8") (pintype "power_in"))
      (node (ref "U100") (pin "J9") (pinfunction "GND_J9") (pintype "power_in"))
      (node (ref "U100") (pin "P1") (pinfunction "GND_P1") (pintype "power_in"))
      (node (ref "U100") (pin "P13") (pinfunction "GND_P13") (pintype "power_in"))
      (node (ref "U100") (pin "P14") (pinfunction "GND_P14") (pintype "power_in"))
      (node (ref "U600") (pin "15") (pinfunction "GND_15") (pintype "power_in"))
      (node (ref "U600") (pin "3") (pinfunction "PGND_3") (pintype "power_in"))
      (node (ref "U600") (pin "9") (pinfunction "GND_9") (pintype "power_in"))
      (node (ref "U601") (pin "3") (pinfunction "VSS_3") (pintype "power_in"))
      (node (ref "U604") (pin "1") (pinfunction "GND_1") (pintype "passive"))
      (node (ref "U605") (pin "1") (pinfunction "GND_1") (pintype "power_in"))
      (node (ref "U606") (pin "3") (pinfunction "GND_3") (pintype "passive"))
      (node (ref "U606") (pin "6") (pinfunction "GND_6") (pintype "passive"))
    )
    (net (code "4") (name "Net-(D600-A)") (class "Default")
      (node (ref "D600") (pin "1") (pinfunction "A_1") (pintype "passive"))
      (node (ref "R600") (pin "1") (pinfunction "1_1") (pintype "passive"))
    )
    (net (code "5") (name "Net-(D600-K)") (class "Default")
      (node (ref "D600") (pin "2") (pinfunction "K_2") (pintype "passive"))
      (node (ref "U601") (pin "8") (pinfunction "~{CHG}_8") (pintype "output"))
    )
    (net (code "6") (name "Net-(J600-SHIELD)") (class "Default")
      (node (ref "J600") (pin "6") (pinfunction "SHIELD_6") (pintype "passive"))
      (node (ref "L602") (pin "1") (pinfunction "1_1") (pintype "passive"))
    )
    (net (code "7") (name "Net-(U600-EN)") (class "Default")
      (node (ref "C603") (pin "2") (pinfunction "2_2") (pintype "passive"))
      (node (ref "R602") (pin "1") (pinfunction "1_1") (pintype "passive"))
      (node (ref "U600") (pin "6") (pinfunction "EN_6") (pintype "input"))
      (node (ref "U600") (pin "7") (pinfunction "PS/SYNC_7") (pintype "input"))
      (node (ref "U600") (pin "8") (pinfunction "VINA_8") (pintype "input"))
    )
    (net (code "8") (name "Net-(U600-FB)") (class "Default")
      (node (ref "C601") (pin "2") (pinfunction "2_2") (pintype "passive"))
      (node (ref "C602") (pin "2") (pinfunction "2_2") (pintype "passive"))
      (node (ref "R601") (pin "1") (pinfunction "1_1") (pintype "passive"))
      (node (ref "U600") (pin "1") (pinfunction "VOUT_1") (pintype "output"))
      (node (ref "U600") (pin "10") (pinfunction "FB_10") (pintype "input"))
    )
    (net (code "9") (name "Net-(U600-L1)") (class "Default")
      (node (ref "L600") (pin "1") (pinfunction "1_1") (pintype "passive"))
      (node (ref "U600") (pin "4") (pinfunction "L1_4") (pintype "input"))
    )
    (net (code "10") (name "Net-(U600-L2)") (class "Default")
      (node (ref "L600") (pin "2") (pinfunction "2_2") (pintype "passive"))
      (node (ref "U600") (pin "2") (pinfunction "L2_2") (pintype "input"))
    )
    (net (code "11") (name "Net-(U601-IN)") (class "Default")
      (node (ref "R603") (pin "1") (pinfunction "1_1") (pintype "passive"))
      (node (ref "U601") (pin "1") (pinfunction "IN_1") (pintype "input"))
    )
    (net (code "12") (name "Net-(U601-ISET)") (class "Default")
      (node (ref "R605") (pin "2") (pinfunction "2_2") (pintype "passive"))
      (node (ref "U601") (pin "2") (pinfunction "ISET_2") (pintype "input"))
    )
    (net (code "13") (name "Net-(U601-ISET2)") (class "Default")
      (node (ref "R607") (pin "2") (pinfunction "2_2") (pintype "passive"))
      (node (ref "R608") (pin "1") (pinfunction "1_1") (pintype "passive"))
      (node (ref "U601") (pin "7") (pinfunction "ISET2_7") (pintype "input"))
    )
    (net (code "14") (name "Net-(U601-OUT)") (class "Default")
      (node (ref "R600") (pin "2") (pinfunction "2_2") (pintype "passive"))
      (node (ref "R604") (pin "2") (pinfunction "2_2") (pintype "passive"))
      (node (ref "U601") (pin "10") (pinfunction "OUT_10") (pintype "output"))
    )
    (net (code "15") (name "Net-(U601-PRETERM)") (class "Default")
      (node (ref "R606") (pin "1") (pinfunction "1_1") (pintype "passive"))
      (node (ref "U601") (pin "4") (pinfunction "PRETERM_4") (pintype "input"))
    )
    (net (code "16") (name "Net-(U601-~{PG})") (class "Default")
      (node (ref "TP600") (pin "1") (pinfunction "1_1") (pintype "passive"))
      (node (ref "U601") (pin "5") (pinfunction "~{PG}_5") (pintype "output"))
    )
    (net (code "17") (name "Net-(U605-OUT)") (class "Default")
      (node (ref "C636") (pin "2") (pinfunction "2_2") (pintype "passive"))
      (node (ref "R611") (pin "1") (pinfunction "1_1") (pintype "passive"))
      (node (ref "U605") (pin "2") (pinfunction "OUT_2") (pintype "power_in"))
      (node (ref "U605") (pin "4") (pinfunction "TAB_4") (pintype "power_in"))
    )
    (net (code "18") (name "Net-(U606-FB)") (class "Default")
      (node (ref "R613") (pin "1") (pinfunction "1_1") (pintype "passive"))
      (node (ref "R615") (pin "2") (pinfunction "2_2") (pintype "passive"))
      (node (ref "U606") (pin "4") (pinfunction "FB_4") (pintype "passive"))
    )
    (net (code "19") (name "Net-(U606-VOUT)") (class "Default")
      (node (ref "R612") (pin "2") (pinfunction "2_2") (pintype "passive"))
      (node (ref "R613") (pin "2") (pinfunction "2_2") (pintype "passive"))
      (node (ref "U606") (pin "2") (pinfunction "VOUT_2") (pintype "passive"))
    )
    (net (code "20") (name "VBAT") (class "Default")
      (node (ref "C600") (pin "2") (pinfunction "2_2") (pintype "passive"))
      (node (ref "C605") (pin "2") (pinfunction "2_2") (pintype "passive"))
      (node (ref "P600") (pin "3") (pinfunction "3_3") (pintype "passive"))
      (node (ref "R602") (pin "2") (pinfunction "2_2") (pintype "passive"))
      (node (ref "R604") (pin "1") (pinfunction "1_1") (pintype "passive"))
      (node (ref "U600") (pin "5") (pinfunction "VIN_5") (pintype "input"))
    )
    (net (code "21") (name "VBUS") (class "Default")
      (node (ref "C604") (pin "2") (pinfunction "2_2") (pintype "passive"))
      (node (ref "J600") (pin "1") (pinfunction "VBUS_1") (pintype "passive"))
      (node (ref "R603") (pin "2") (pinfunction "2_2") (pintype "passive"))
    )
    (net (code "22") (name "VCC1V3") (class "Default")
      (node (ref "C637") (pin "2") (pinfunction "2_2") (pintype "passive"))
      (node (ref "C638") (pin "2") (pinfunction "2_2") (pintype "passive"))
      (node (ref "C639") (pin "2") (pinfunction "2_2") (pintype "passive"))
      (node (ref "C640") (pin "2") (pinfunction "2_2") (pintype "passive"))
      (node (ref "C641") (pin "2") (pinfunction "2_2") (pintype "passive"))
      (node (ref "C642") (pin "2") (pinfunction "2_2") (pintype "passive"))
      (node (ref "C643") (pin "2") (pinfunction "2_2") (pintype "passive"))
      (node (ref "C644") (pin "2") (pinfunction "2_2") (pintype "passive"))
      (node (ref "C645") (pin "2") (pinfunction "2_2") (pintype "passive"))
      (node (ref "C646") (pin "2") (pinfunction "2_2") (pintype "passive"))
      (node (ref "C647") (pin "2") (pinfunction "2_2") (pintype "passive"))
      (node (ref "C648") (pin "2") (pinfunction "2_2") (pintype "passive"))
      (node (ref "C651") (pin "1") (pinfunction "1_1") (pintype "passive"))
      (node (ref "R612") (pin "1") (pinfunction "1_1") (pintype "passive"))
      (node (ref "U100") (pin "C9") (pinfunction "VDDINT_C9") (pintype "power_in"))
      (node (ref "U100") (pin "E10") (pinfunction "VDDINT_E10") (pintype "power_in"))
      (node (ref "U100") (pin "E7") (pinfunction "VDDINT_E7") (pintype "power_in"))
      (node (ref "U100") (pin "E8") (pinfunction "VDDINT_E8") (pintype "power_in"))
      (node (ref "U100") (pin "E9") (pinfunction "VDDINT_E9") (pintype "power_in"))
      (node (ref "U100") (pin "F10") (pinfunction "VDDINT_F10") (pintype "power_in"))
      (node (ref "U100") (pin "F3") (pinfunction "VDDINT_F3") (pintype "power_in"))
      (node (ref "U100") (pin "G10") (pinfunction "VDDINT_G10") (pintype "power_in"))
      (node (ref "U100") (pin "G3") (pinfunction "VDDINT_G3") (pintype "power_in"))
      (node (ref "U100") (pin "H10") (pinfunction "VDDINT_H10") (pintype "power_in"))
      (node (ref "U100") (pin "J10") (pinfunction "VDDINT_J10") (pintype "power_in"))
    )
    (net (code "23") (name "VCC1V8") (class "Default")
      (node (ref "R611") (pin "2") (pinfunction "2_2") (pintype "passive"))
    )
    (net (code "24") (name "VCC2V5") (class "Default")
      (node (ref "C612") (pin "2") (pinfunction "2_2") (pintype "passive"))
      (node (ref "U100") (pin "B1") (pinfunction "VDDOTP_B1") (pintype "power_in"))
      (node (ref "U100") (pin "D3") (pinfunction "VPPOTP_D3") (pintype "power_in"))
      (node (ref "U604") (pin "2") (pinfunction "OUT_2") (pintype "passive"))
    )
    (net (code "25") (name "VCC3V3") (class "Default")
      (node (ref "C610") (pin "1") (pinfunction "1_1") (pintype "passive"))
      (node (ref "C611") (pin "2") (pinfunction "2_2") (pintype "passive"))
      (node (ref "C613") (pin "2") (pinfunction "2_2") (pintype "passive"))
      (node (ref "C614") (pin "2") (pinfunction "2_2") (pintype "passive"))
      (node (ref "C615") (pin "2") (pinfunction "2_2") (pintype "passive"))
      (node (ref "C616") (pin "2") (pinfunction "2_2") (pintype "passive"))
      (node (ref "C617") (pin "2") (pinfunction "2_2") (pintype "passive"))
      (node (ref "C618") (pin "2") (pinfunction "2_2") (pintype "passive"))
      (node (ref "C619") (pin "2") (pinfunction "2_2") (pintype "passive"))
      (node (ref "C620") (pin "2") (pinfunction "2_2") (pintype "passive"))
      (node (ref "C621") (pin "2") (pinfunction "2_2") (pintype "passive"))
      (node (ref "C622") (pin "2") (pinfunction "2_2") (pintype "passive"))
      (node (ref "C623") (pin "2") (pinfunction "2_2") (pintype "passive"))
      (node (ref "C624") (pin "2") (pinfunction "2_2") (pintype "passive"))
      (node (ref "C625") (pin "2") (pinfunction "2_2") (pintype "passive"))
      (node (ref "C626") (pin "2") (pinfunction "2_2") (pintype "passive"))
      (node (ref "C627") (pin "2") (pinfunction "2_2") (pintype "passive"))
      (node (ref "C628") (pin "2") (pinfunction "2_2") (pintype "passive"))
      (node (ref "C629") (pin "2") (pinfunction "2_2") (pintype "passive"))
      (node (ref "C630") (pin "2") (pinfunction "2_2") (pintype "passive"))
      (node (ref "C631") (pin "2") (pinfunction "2_2") (pintype "passive"))
      (node (ref "C632") (pin "2") (pinfunction "2_2") (pintype "passive"))
      (node (ref "C633") (pin "2") (pinfunction "2_2") (pintype "passive"))
      (node (ref "C634") (pin "2") (pinfunction "2_2") (pintype "passive"))
      (node (ref "C635") (pin "2") (pinfunction "2_2") (pintype "passive"))
      (node (ref "C649") (pin "1") (pinfunction "1_1") (pintype "passive"))
      (node (ref "C650") (pin "2") (pinfunction "2_2") (pintype "passive"))
      (node (ref "C652") (pin "2") (pinfunction "2_2") (pintype "passive"))
      (node (ref "C653") (pin "2") (pinfunction "2_2") (pintype "passive"))
      (node (ref "C654") (pin "2") (pinfunction "2_2") (pintype "passive"))
      (node (ref "C655") (pin "2") (pinfunction "2_2") (pintype "passive"))
      (node (ref "C656") (pin "2") (pinfunction "2_2") (pintype "passive"))
      (node (ref "R601") (pin "2") (pinfunction "2_2") (pintype "passive"))
      (node (ref "R607") (pin "1") (pinfunction "1_1") (pintype "passive"))
      (node (ref "R614") (pin "1") (pinfunction "1_1") (pintype "passive"))
      (node (ref "U100") (pin "B12") (pinfunction "VDDRTC_B12") (pintype "power_in"))
      (node (ref "U100") (pin "B13") (pinfunction "VDDEXT_B13") (pintype "power_in"))
      (node (ref "U100") (pin "B9") (pinfunction "VDDEXT_B9") (pintype "power_in"))
      (node (ref "U100") (pin "C10") (pinfunction "VDDEXT_C10") (pintype "power_in"))
      (node (ref "U100") (pin "C5") (pinfunction "VDDEXT_C5") (pintype "power_in"))
      (node (ref "U100") (pin "C6") (pinfunction "VDDEXT_C6") (pintype "power_in"))
      (node (ref "U100") (pin "C8") (pinfunction "VDDEXT_C8") (pintype "power_in"))
      (node (ref "U100") (pin "D12") (pinfunction "VDDFLASH_D12") (pintype "power_in"))
      (node (ref "U100") (pin "E1") (pinfunction "VDDFLASH_E1") (pintype "power_in"))
      (node (ref "U100") (pin "E12") (pinfunction "VDDMEM_E12") (pintype "power_in"))
      (node (ref "U100") (pin "E5") (pinfunction "VDDEXT_E5") (pintype "power_in"))
      (node (ref "U100") (pin "E6") (pinfunction "VDDEXT_E6") (pintype "power_in"))
      (node (ref "U100") (pin "F5") (pinfunction "VDDEXT_F5") (pintype "power_in"))
      (node (ref "U100") (pin "G5") (pinfunction "VDDEXT_G5") (pintype "power_in"))
      (node (ref "U100") (pin "H5") (pinfunction "VDDEXT_H5") (pintype "power_in"))
      (node (ref "U100") (pin "J2") (pinfunction "VDDFLASH_J2") (pintype "power_in"))
      (node (ref "U100") (pin "J5") (pinfunction "VDDMEM_J5") (pintype "power_in"))
      (node (ref "U100") (pin "K10") (pinfunction "VDDMEM_K10") (pintype "power_in"))
      (node (ref "U100") (pin "K5") (pinfunction "VDDMEM_K5") (pintype "power_in"))
      (node (ref "U100") (pin "K6") (pinfunction "VDDMEM_K6") (pintype "power_in"))
      (node (ref "U100") (pin "K7") (pinfunction "VDDMEM_K7") (pintype "power_in"))
      (node (ref "U100") (pin "K8") (pinfunction "VDDMEM_K8") (pintype "power_in"))
      (node (ref "U100") (pin "K9") (pinfunction "VDDMEM_K9") (pintype "power_in"))
      (node (ref "U604") (pin "3") (pinfunction "IN_3") (pintype "passive"))
      (node (ref "U605") (pin "3") (pinfunction "IN_3") (pintype "power_in"))
      (node (ref "U606") (pin "1") (pinfunction "VIN_1") (pintype "passive"))
    )
    (net (code "26") (name "unconnected-(J600-D+-Pad3)") (class "Default")
      (node (ref "J600") (pin "3") (pinfunction "D+_3") (pintype "passive+no_connect"))
    )
    (net (code "27") (name "unconnected-(J600-D--Pad2)") (class "Default")
      (node (ref "J600") (pin "2") (pinfunction "D-_2") (pintype "passive+no_connect"))
    )
    (net (code "28") (name "unconnected-(U601-NC-Pad6)") (class "Default")
      (node (ref "U601") (pin "6") (pinfunction "NC_6") (pintype "passive+no_connect"))
    )
  )
)
